# Pendulum_Lamp_PCB.net
KiCad netlist of a schematic drawn in EAGLE
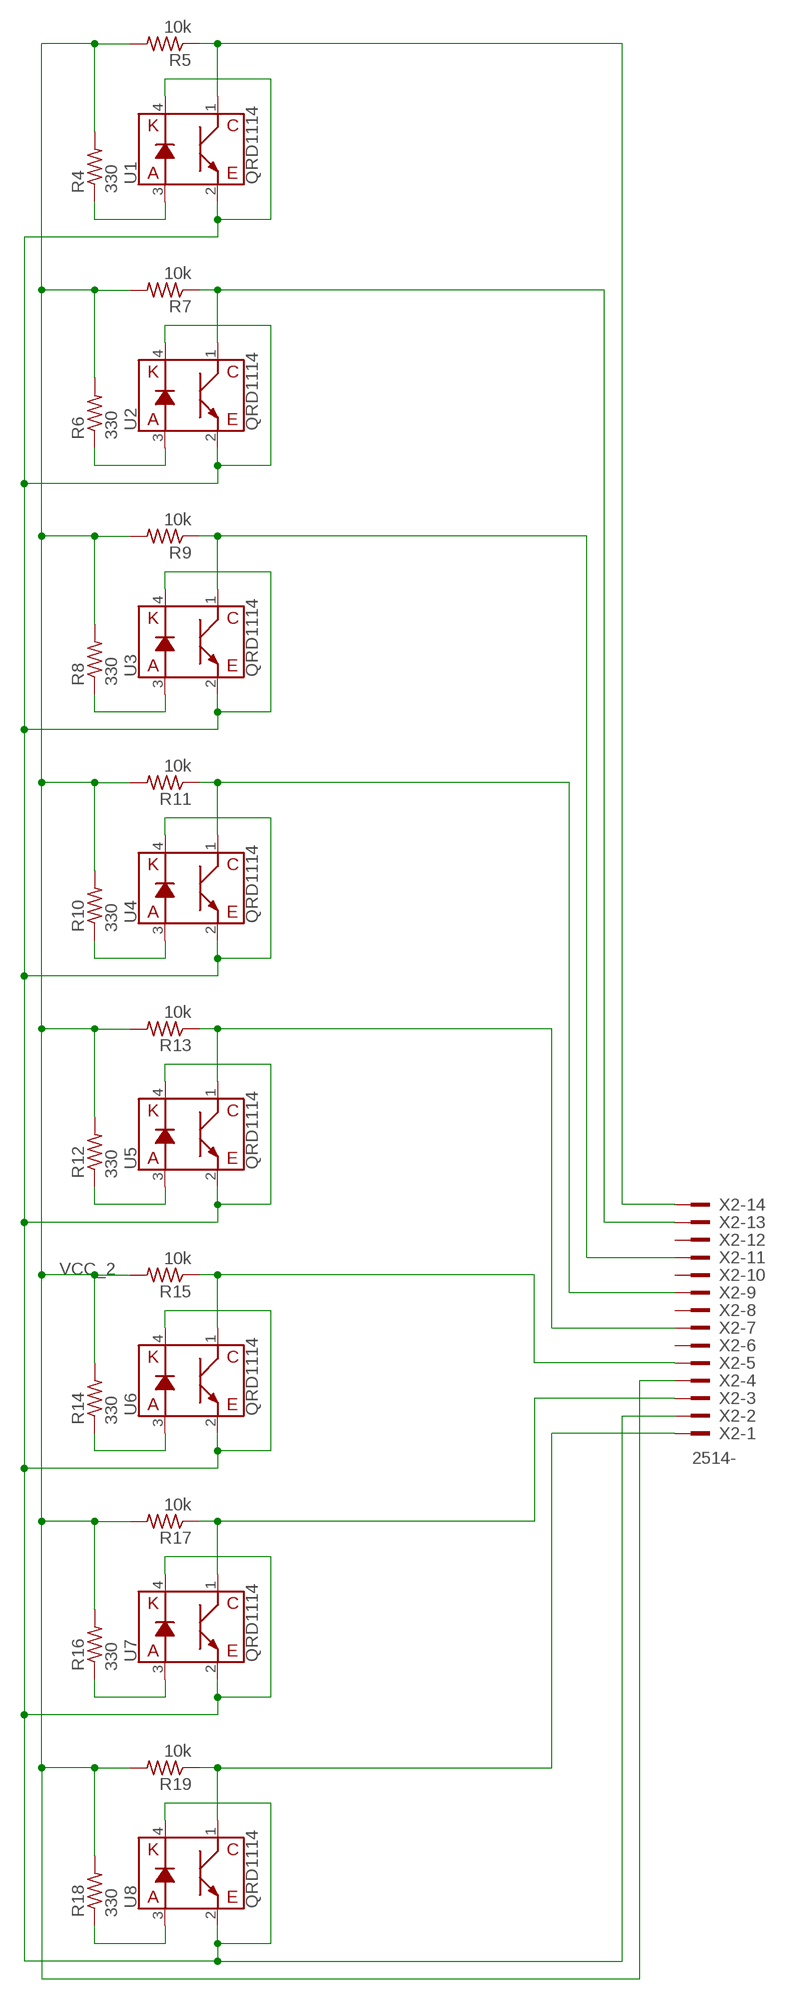
[diagram p0: schematic, sheet 1]

(export (version "E")
  (design (tool "Eeschema 10.0.6"))
  (components
    (comp (ref "R4")
      (value "330")
      (footprint "eagle-import:0204_7")
      (libsource (lib "eagle-import") (part "R-US_0204/7"))
    )
    (comp (ref "R5")
      (value "10k")
      (footprint "eagle-import:0204_7")
      (libsource (lib "eagle-import") (part "R-US_0204/7"))
    )
    (comp (ref "R6")
      (value "330")
      (footprint "eagle-import:0204_7")
      (libsource (lib "eagle-import") (part "R-US_0204/7"))
    )
    (comp (ref "R7")
      (value "10k")
      (footprint "eagle-import:0204_7")
      (libsource (lib "eagle-import") (part "R-US_0204/7"))
    )
    (comp (ref "R8")
      (value "330")
      (footprint "eagle-import:0204_7")
      (libsource (lib "eagle-import") (part "R-US_0204/7"))
    )
    (comp (ref "R9")
      (value "10k")
      (footprint "eagle-import:0204_7")
      (libsource (lib "eagle-import") (part "R-US_0204/7"))
    )
    (comp (ref "R10")
      (value "330")
      (footprint "eagle-import:0204_7")
      (libsource (lib "eagle-import") (part "R-US_0204/7"))
    )
    (comp (ref "R11")
      (value "10k")
      (footprint "eagle-import:0204_7")
      (libsource (lib "eagle-import") (part "R-US_0204/7"))
    )
    (comp (ref "R12")
      (value "330")
      (footprint "eagle-import:0204_7")
      (libsource (lib "eagle-import") (part "R-US_0204/7"))
    )
    (comp (ref "R13")
      (value "10k")
      (footprint "eagle-import:0204_7")
      (libsource (lib "eagle-import") (part "R-US_0204/7"))
    )
    (comp (ref "R14")
      (value "330")
      (footprint "eagle-import:0204_7")
      (libsource (lib "eagle-import") (part "R-US_0204/7"))
    )
    (comp (ref "R15")
      (value "10k")
      (footprint "eagle-import:0204_7")
      (libsource (lib "eagle-import") (part "R-US_0204/7"))
    )
    (comp (ref "R16")
      (value "330")
      (footprint "eagle-import:0204_7")
      (libsource (lib "eagle-import") (part "R-US_0204/7"))
    )
    (comp (ref "R17")
      (value "10k")
      (footprint "eagle-import:0204_7")
      (libsource (lib "eagle-import") (part "R-US_0204/7"))
    )
    (comp (ref "R18")
      (value "330")
      (footprint "eagle-import:0204_7")
      (libsource (lib "eagle-import") (part "R-US_0204/7"))
    )
    (comp (ref "R19")
      (value "10k")
      (footprint "eagle-import:0204_7")
      (libsource (lib "eagle-import") (part "R-US_0204/7"))
    )
    (comp (ref "U1")
      (value "QRD1114")
      (footprint "eagle-import:QRD1114")
      (libsource (lib "eagle-import") (part "QRD1114"))
    )
    (comp (ref "U2")
      (value "QRD1114")
      (footprint "eagle-import:QRD1114")
      (libsource (lib "eagle-import") (part "QRD1114"))
    )
    (comp (ref "U3")
      (value "QRD1114")
      (footprint "eagle-import:QRD1114")
      (libsource (lib "eagle-import") (part "QRD1114"))
    )
    (comp (ref "U4")
      (value "QRD1114")
      (footprint "eagle-import:QRD1114")
      (libsource (lib "eagle-import") (part "QRD1114"))
    )
    (comp (ref "U5")
      (value "QRD1114")
      (footprint "eagle-import:QRD1114")
      (libsource (lib "eagle-import") (part "QRD1114"))
    )
    (comp (ref "U6")
      (value "QRD1114")
      (footprint "eagle-import:QRD1114")
      (libsource (lib "eagle-import") (part "QRD1114"))
    )
    (comp (ref "U7")
      (value "QRD1114")
      (footprint "eagle-import:QRD1114")
      (libsource (lib "eagle-import") (part "QRD1114"))
    )
    (comp (ref "U8")
      (value "QRD1114")
      (footprint "eagle-import:QRD1114")
      (libsource (lib "eagle-import") (part "QRD1114"))
    )
    (comp (ref "X2")
      (value "2514-")
      (footprint "eagle-import:PAK100_2500-14")
      (libsource (lib "eagle-import") (part "2514-"))
    )
  )
  (nets
    (net (code "1") (name "/VCC_2") (class "Default")
      (node (ref "R10") (pin "2") (pinfunction "2_2") (pintype "passive"))
      (node (ref "R11") (pin "2") (pinfunction "2_2") (pintype "passive"))
      (node (ref "R12") (pin "2") (pinfunction "2_2") (pintype "passive"))
      (node (ref "R13") (pin "2") (pinfunction "2_2") (pintype "passive"))
      (node (ref "R14") (pin "2") (pinfunction "2_2") (pintype "passive"))
      (node (ref "R15") (pin "2") (pinfunction "2_2") (pintype "passive"))
      (node (ref "R16") (pin "2") (pinfunction "2_2") (pintype "passive"))
      (node (ref "R17") (pin "2") (pinfunction "2_2") (pintype "passive"))
      (node (ref "R18") (pin "2") (pinfunction "2_2") (pintype "passive"))
      (node (ref "R19") (pin "2") (pinfunction "2_2") (pintype "passive"))
      (node (ref "R4") (pin "2") (pinfunction "2_2") (pintype "passive"))
      (node (ref "R5") (pin "2") (pinfunction "2_2") (pintype "passive"))
      (node (ref "R6") (pin "2") (pinfunction "2_2") (pintype "passive"))
      (node (ref "R7") (pin "2") (pinfunction "2_2") (pintype "passive"))
      (node (ref "R8") (pin "2") (pinfunction "2_2") (pintype "passive"))
      (node (ref "R9") (pin "2") (pinfunction "2_2") (pintype "passive"))
      (node (ref "X2") (pin "4") (pinfunction "KL_4") (pintype "passive"))
    )
    (net (code "2") (name "Net-(U1-A)") (class "Default")
      (node (ref "R4") (pin "1") (pinfunction "1_1") (pintype "passive"))
      (node (ref "U1") (pin "3") (pinfunction "A_3") (pintype "bidirectional"))
    )
    (net (code "3") (name "Net-(U1-C)") (class "Default")
      (node (ref "R5") (pin "1") (pinfunction "1_1") (pintype "passive"))
      (node (ref "U1") (pin "1") (pinfunction "C_1") (pintype "bidirectional"))
      (node (ref "X2") (pin "14") (pinfunction "KL_14") (pintype "passive"))
    )
    (net (code "4") (name "Net-(U1-E)") (class "Default")
      (node (ref "U1") (pin "2") (pinfunction "E_2") (pintype "bidirectional"))
      (node (ref "U1") (pin "4") (pinfunction "K_4") (pintype "bidirectional"))
      (node (ref "U2") (pin "2") (pinfunction "E_2") (pintype "bidirectional"))
      (node (ref "U2") (pin "4") (pinfunction "K_4") (pintype "bidirectional"))
      (node (ref "U3") (pin "2") (pinfunction "E_2") (pintype "bidirectional"))
      (node (ref "U3") (pin "4") (pinfunction "K_4") (pintype "bidirectional"))
      (node (ref "U4") (pin "2") (pinfunction "E_2") (pintype "bidirectional"))
      (node (ref "U4") (pin "4") (pinfunction "K_4") (pintype "bidirectional"))
      (node (ref "U5") (pin "2") (pinfunction "E_2") (pintype "bidirectional"))
      (node (ref "U5") (pin "4") (pinfunction "K_4") (pintype "bidirectional"))
      (node (ref "U6") (pin "2") (pinfunction "E_2") (pintype "bidirectional"))
      (node (ref "U6") (pin "4") (pinfunction "K_4") (pintype "bidirectional"))
      (node (ref "U7") (pin "2") (pinfunction "E_2") (pintype "bidirectional"))
      (node (ref "U7") (pin "4") (pinfunction "K_4") (pintype "bidirectional"))
      (node (ref "U8") (pin "2") (pinfunction "E_2") (pintype "bidirectional"))
      (node (ref "U8") (pin "4") (pinfunction "K_4") (pintype "bidirectional"))
      (node (ref "X2") (pin "2") (pinfunction "KL_2") (pintype "passive"))
    )
    (net (code "5") (name "Net-(U2-A)") (class "Default")
      (node (ref "R6") (pin "1") (pinfunction "1_1") (pintype "passive"))
      (node (ref "U2") (pin "3") (pinfunction "A_3") (pintype "bidirectional"))
    )
    (net (code "6") (name "Net-(U2-C)") (class "Default")
      (node (ref "R7") (pin "1") (pinfunction "1_1") (pintype "passive"))
      (node (ref "U2") (pin "1") (pinfunction "C_1") (pintype "bidirectional"))
      (node (ref "X2") (pin "13") (pinfunction "KL_13") (pintype "passive"))
    )
    (net (code "7") (name "Net-(U3-A)") (class "Default")
      (node (ref "R8") (pin "1") (pinfunction "1_1") (pintype "passive"))
      (node (ref "U3") (pin "3") (pinfunction "A_3") (pintype "bidirectional"))
    )
    (net (code "8") (name "Net-(U3-C)") (class "Default")
      (node (ref "R9") (pin "1") (pinfunction "1_1") (pintype "passive"))
      (node (ref "U3") (pin "1") (pinfunction "C_1") (pintype "bidirectional"))
      (node (ref "X2") (pin "11") (pinfunction "KL_11") (pintype "passive"))
    )
    (net (code "9") (name "Net-(U4-A)") (class "Default")
      (node (ref "R10") (pin "1") (pinfunction "1_1") (pintype "passive"))
      (node (ref "U4") (pin "3") (pinfunction "A_3") (pintype "bidirectional"))
    )
    (net (code "10") (name "Net-(U4-C)") (class "Default")
      (node (ref "R11") (pin "1") (pinfunction "1_1") (pintype "passive"))
      (node (ref "U4") (pin "1") (pinfunction "C_1") (pintype "bidirectional"))
      (node (ref "X2") (pin "9") (pinfunction "KL_9") (pintype "passive"))
    )
    (net (code "11") (name "Net-(U5-A)") (class "Default")
      (node (ref "R12") (pin "1") (pinfunction "1_1") (pintype "passive"))
      (node (ref "U5") (pin "3") (pinfunction "A_3") (pintype "bidirectional"))
    )
    (net (code "12") (name "Net-(U5-C)") (class "Default")
      (node (ref "R13") (pin "1") (pinfunction "1_1") (pintype "passive"))
      (node (ref "U5") (pin "1") (pinfunction "C_1") (pintype "bidirectional"))
      (node (ref "X2") (pin "7") (pinfunction "KL_7") (pintype "passive"))
    )
    (net (code "13") (name "Net-(U6-A)") (class "Default")
      (node (ref "R14") (pin "1") (pinfunction "1_1") (pintype "passive"))
      (node (ref "U6") (pin "3") (pinfunction "A_3") (pintype "bidirectional"))
    )
    (net (code "14") (name "Net-(U6-C)") (class "Default")
      (node (ref "R15") (pin "1") (pinfunction "1_1") (pintype "passive"))
      (node (ref "U6") (pin "1") (pinfunction "C_1") (pintype "bidirectional"))
      (node (ref "X2") (pin "5") (pinfunction "KL_5") (pintype "passive"))
    )
    (net (code "15") (name "Net-(U7-A)") (class "Default")
      (node (ref "R16") (pin "1") (pinfunction "1_1") (pintype "passive"))
      (node (ref "U7") (pin "3") (pinfunction "A_3") (pintype "bidirectional"))
    )
    (net (code "16") (name "Net-(U7-C)") (class "Default")
      (node (ref "R17") (pin "1") (pinfunction "1_1") (pintype "passive"))
      (node (ref "U7") (pin "1") (pinfunction "C_1") (pintype "bidirectional"))
      (node (ref "X2") (pin "3") (pinfunction "KL_3") (pintype "passive"))
    )
    (net (code "17") (name "Net-(U8-A)") (class "Default")
      (node (ref "R18") (pin "1") (pinfunction "1_1") (pintype "passive"))
      (node (ref "U8") (pin "3") (pinfunction "A_3") (pintype "bidirectional"))
    )
    (net (code "18") (name "Net-(U8-C)") (class "Default")
      (node (ref "R19") (pin "1") (pinfunction "1_1") (pintype "passive"))
      (node (ref "U8") (pin "1") (pinfunction "C_1") (pintype "bidirectional"))
      (node (ref "X2") (pin "1") (pinfunction "KL_1") (pintype "passive"))
    )
    (net (code "19") (name "unconnected-(X2B-KL-Pad10)") (class "Default")
      (node (ref "X2") (pin "10") (pinfunction "KL_10") (pintype "passive"))
    )
    (net (code "20") (name "unconnected-(X2D-KL-Pad12)") (class "Default")
      (node (ref "X2") (pin "12") (pinfunction "KL_12") (pintype "passive"))
    )
    (net (code "21") (name "unconnected-(X2K-KL-Pad6)") (class "Default")
      (node (ref "X2") (pin "6") (pinfunction "KL_6") (pintype "passive"))
    )
    (net (code "22") (name "unconnected-(X2M-KL-Pad8)") (class "Default")
      (node (ref "X2") (pin "8") (pinfunction "KL_8") (pintype "passive"))
    )
  )
)
